# uUSB_breakout_v2.net
KiCad netlist of a schematic drawn in EAGLE
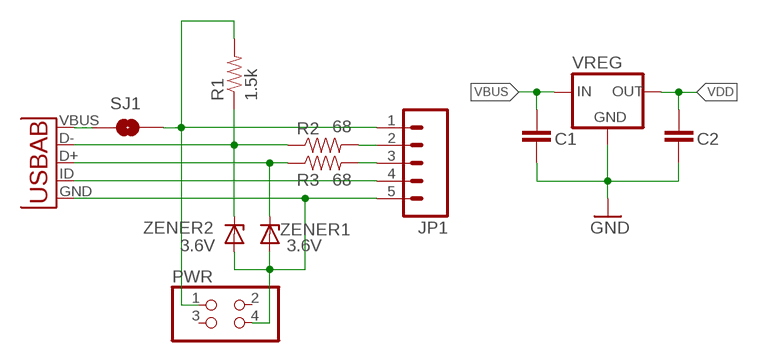
[diagram p0: schematic, sheet 1]

(export (version "E")
  (design (tool "Eeschema 10.0.6"))
  (components
    (comp (ref "C1")
      (value "CAPACITOR_NPOL-0805")
      (footprint "eagle-import:C805")
      (libsource (lib "eagle-import") (part "CAPACITOR_NPOL-0805"))
    )
    (comp (ref "C2")
      (value "CAPACITOR_NPOL-0805")
      (footprint "eagle-import:C805")
      (libsource (lib "eagle-import") (part "CAPACITOR_NPOL-0805"))
    )
    (comp (ref "JP1")
      (value "M05PTH")
      (footprint "eagle-import:1X05")
      (libsource (lib "eagle-import") (part "M05PTH"))
    )
    (comp (ref "PWR")
      (value "PINHD-2X2")
      (footprint "eagle-import:2X02")
      (libsource (lib "eagle-import") (part "PINHD-2X2"))
    )
    (comp (ref "R1")
      (value "1.5k")
      (footprint "eagle-import:0805")
      (libsource (lib "eagle-import") (part "RESISTOR0805-RES"))
    )
    (comp (ref "R2")
      (value "68")
      (footprint "eagle-import:0805")
      (libsource (lib "eagle-import") (part "RESISTOR0805-RES"))
    )
    (comp (ref "R3")
      (value "68")
      (footprint "eagle-import:0805")
      (libsource (lib "eagle-import") (part "RESISTOR0805-RES"))
    )
    (comp (ref "SJ1")
      (value "SOLDERJUMPERNO")
      (footprint "eagle-import:SJ_2S-NO")
      (libsource (lib "eagle-import") (part "SOLDERJUMPERNO"))
    )
    (comp (ref "UUSB")
      (value "USB-AB")
      (footprint "eagle-import:USB-AB-MICRO-SMD")
      (libsource (lib "eagle-import") (part "USB-AB"))
    )
    (comp (ref "VREG")
      (value "V_REG_MIC2920")
      (footprint "eagle-import:SOT223")
      (libsource (lib "eagle-import") (part "V_REG_MIC2920"))
    )
    (comp (ref "ZENER1")
      (value "3.6V")
      (footprint "eagle-import:SOD80C")
      (libsource (lib "eagle-import") (part "ZENER-DIODESOD80C"))
    )
    (comp (ref "ZENER2")
      (value "3.6V")
      (footprint "eagle-import:SOD80C")
      (libsource (lib "eagle-import") (part "ZENER-DIODESOD80C"))
    )
  )
  (nets
    (net (code "1") (name "GND") (class "Default")
      (node (ref "C1") (pin "2") (pinfunction "2_2") (pintype "passive"))
      (node (ref "C2") (pin "2") (pinfunction "2_2") (pintype "passive"))
      (node (ref "JP1") (pin "5") (pinfunction "5_5") (pintype "passive"))
      (node (ref "PWR") (pin "4") (pinfunction "4_4") (pintype "passive"))
      (node (ref "UUSB") (pin "GND") (pinfunction "GND_GND") (pintype "bidirectional"))
      (node (ref "VREG") (pin "2") (pinfunction "GND_2") (pintype "input"))
      (node (ref "VREG") (pin "4") (pinfunction "GND_4") (pintype "input"))
      (node (ref "ZENER1") (pin "A") (pinfunction "A_A") (pintype "passive"))
      (node (ref "ZENER2") (pin "A") (pinfunction "A_A") (pintype "passive"))
    )
    (net (code "2") (name "Net-(JP1-Pad2)") (class "Default")
      (node (ref "JP1") (pin "2") (pinfunction "2_2") (pintype "passive"))
      (node (ref "R2") (pin "2") (pinfunction "2_2") (pintype "passive"))
    )
    (net (code "3") (name "Net-(JP1-Pad3)") (class "Default")
      (node (ref "JP1") (pin "3") (pinfunction "3_3") (pintype "passive"))
      (node (ref "R3") (pin "2") (pinfunction "2_2") (pintype "passive"))
    )
    (net (code "4") (name "Net-(R1-Pad1)") (class "Default")
      (node (ref "R1") (pin "1") (pinfunction "1_1") (pintype "passive"))
      (node (ref "R2") (pin "1") (pinfunction "1_1") (pintype "passive"))
      (node (ref "UUSB") (pin "D-") (pinfunction "D-_D-") (pintype "bidirectional"))
      (node (ref "ZENER2") (pin "C") (pinfunction "C_C") (pintype "passive"))
    )
    (net (code "5") (name "Net-(R3-Pad1)") (class "Default")
      (node (ref "R3") (pin "1") (pinfunction "1_1") (pintype "passive"))
      (node (ref "UUSB") (pin "D+") (pinfunction "D+_D+") (pintype "bidirectional"))
      (node (ref "ZENER1") (pin "C") (pinfunction "C_C") (pintype "passive"))
    )
    (net (code "6") (name "Net-(UUSB-USBID)") (class "Default")
      (node (ref "JP1") (pin "4") (pinfunction "4_4") (pintype "passive"))
      (node (ref "UUSB") (pin "ID") (pinfunction "USBID_ID") (pintype "bidirectional"))
    )
    (net (code "7") (name "VBUS") (class "Default")
      (node (ref "C1") (pin "1") (pinfunction "1_1") (pintype "passive"))
      (node (ref "SJ1") (pin "1") (pinfunction "1_1") (pintype "passive"))
      (node (ref "UUSB") (pin "VBUS") (pinfunction "VBUS_VBUS") (pintype "bidirectional"))
      (node (ref "VREG") (pin "1") (pinfunction "IN_1") (pintype "input"))
    )
    (net (code "8") (name "VDD") (class "Default")
      (node (ref "C2") (pin "1") (pinfunction "1_1") (pintype "passive"))
      (node (ref "JP1") (pin "1") (pinfunction "1_1") (pintype "passive"))
      (node (ref "PWR") (pin "1") (pinfunction "1_1") (pintype "passive"))
      (node (ref "R1") (pin "2") (pinfunction "2_2") (pintype "passive"))
      (node (ref "SJ1") (pin "2") (pinfunction "2_2") (pintype "passive"))
      (node (ref "VREG") (pin "3") (pinfunction "OUT_3") (pintype "output"))
    )
    (net (code "9") (name "unconnected-(PWR-Pad2)") (class "Default")
      (node (ref "PWR") (pin "2") (pinfunction "2_2") (pintype "passive"))
    )
    (net (code "10") (name "unconnected-(PWR-Pad3)") (class "Default")
      (node (ref "PWR") (pin "3") (pinfunction "3_3") (pintype "passive"))
    )
  )
)
